# FT232_BreakOutBoard_rev2.net
KiCad netlist of a schematic drawn in EAGLE
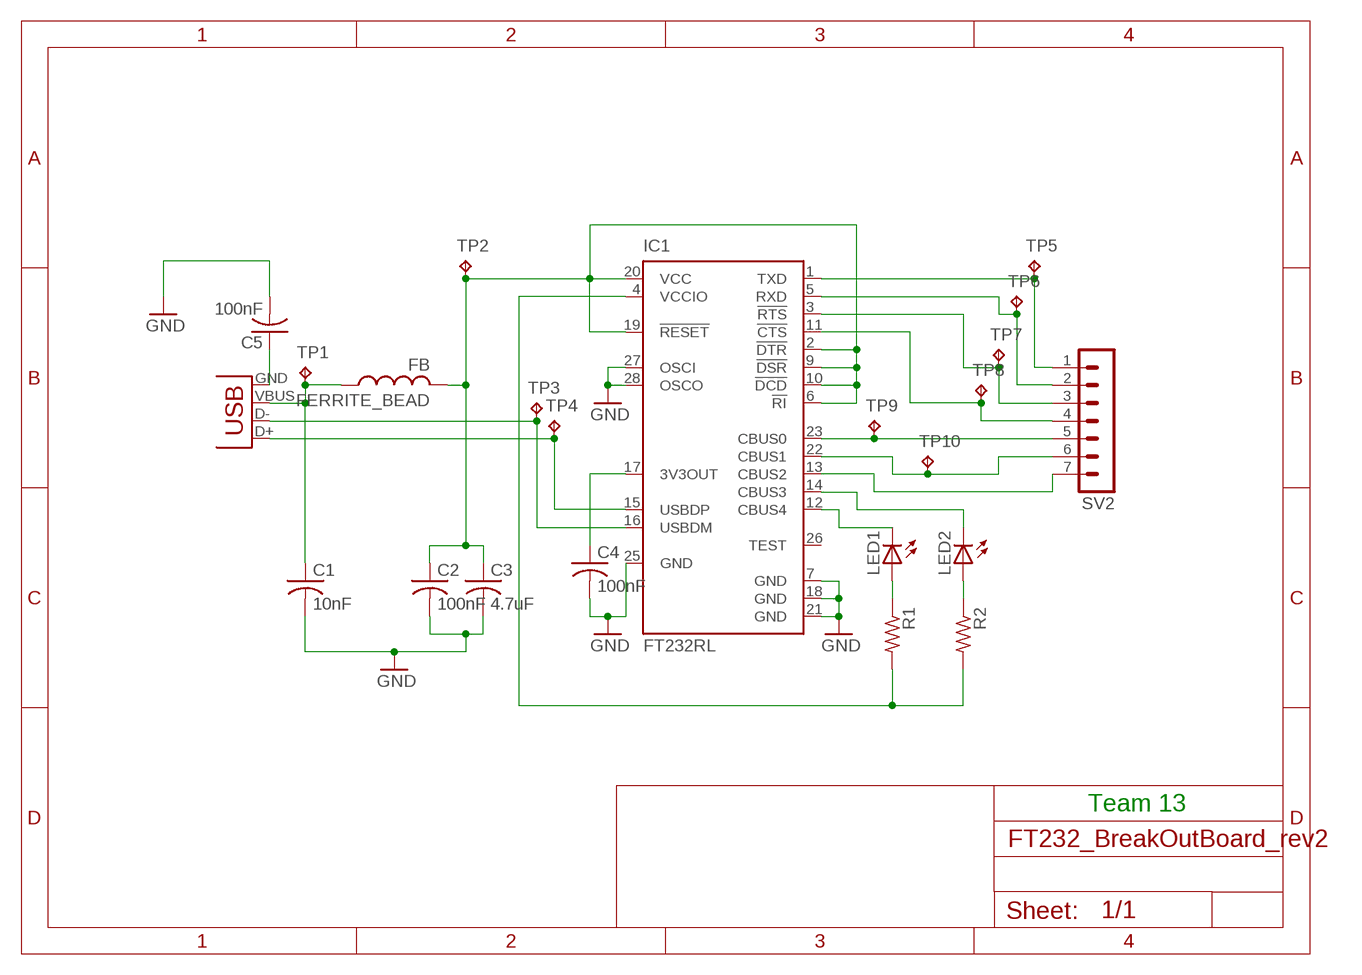
[diagram p0: schematic, sheet 1]

(export (version "E")
  (design (tool "Eeschema 10.0.6"))
  (components
    (comp (ref "C1")
      (value "10nF")
      (footprint "eagle-import:C0805")
      (libsource (lib "eagle-import") (part "C-USC0805"))
    )
    (comp (ref "C2")
      (value "100nF")
      (footprint "eagle-import:C0805")
      (libsource (lib "eagle-import") (part "C-USC0805"))
    )
    (comp (ref "C3")
      (value "4.7uF")
      (footprint "eagle-import:C0805")
      (libsource (lib "eagle-import") (part "C-USC0805"))
    )
    (comp (ref "C4")
      (value "100nF")
      (footprint "eagle-import:C0805")
      (libsource (lib "eagle-import") (part "C-USC0805"))
    )
    (comp (ref "C5")
      (value "100nF")
      (footprint "eagle-import:C0805")
      (libsource (lib "eagle-import") (part "C-USC0805"))
    )
    (comp (ref "FERRITE_BEAD")
      (value "FB")
      (footprint "eagle-import:FB")
      (libsource (lib "eagle-import") (part "FB"))
    )
    (comp (ref "IC1")
      (value "FT232RL")
      (footprint "eagle-import:SSOP28")
      (libsource (lib "eagle-import") (part "FT232RL"))
    )
    (comp (ref "LED1")
      (value "LEDCHIPLED_0805")
      (footprint "eagle-import:CHIPLED_0805")
      (libsource (lib "eagle-import") (part "LEDCHIPLED_0805"))
    )
    (comp (ref "LED2")
      (value "LEDCHIPLED_0805")
      (footprint "eagle-import:CHIPLED_0805")
      (libsource (lib "eagle-import") (part "LEDCHIPLED_0805"))
    )
    (comp (ref "R1")
      (value "R-US_R0805")
      (footprint "eagle-import:R0805")
      (libsource (lib "eagle-import") (part "R-US_R0805"))
    )
    (comp (ref "R2")
      (value "R-US_R0805")
      (footprint "eagle-import:R0805")
      (libsource (lib "eagle-import") (part "R-US_R0805"))
    )
    (comp (ref "SV2")
      (value "MA07-1")
      (footprint "eagle-import:MA07-1")
      (libsource (lib "eagle-import") (part "MA07-1"))
    )
    (comp (ref "TP1")
      (value "TPB1,27")
      (footprint "eagle-import:B1,27")
      (libsource (lib "eagle-import") (part "TPB1,27"))
    )
    (comp (ref "TP2")
      (value "TPB1,27")
      (footprint "eagle-import:B1,27")
      (libsource (lib "eagle-import") (part "TPB1,27"))
    )
    (comp (ref "TP3")
      (value "TPB1,27")
      (footprint "eagle-import:B1,27")
      (libsource (lib "eagle-import") (part "TPB1,27"))
    )
    (comp (ref "TP4")
      (value "TPB1,27")
      (footprint "eagle-import:B1,27")
      (libsource (lib "eagle-import") (part "TPB1,27"))
    )
    (comp (ref "TP5")
      (value "TPB1,27")
      (footprint "eagle-import:B1,27")
      (libsource (lib "eagle-import") (part "TPB1,27"))
    )
    (comp (ref "TP6")
      (value "TPB1,27")
      (footprint "eagle-import:B1,27")
      (libsource (lib "eagle-import") (part "TPB1,27"))
    )
    (comp (ref "TP7")
      (value "TPB1,27")
      (footprint "eagle-import:B1,27")
      (libsource (lib "eagle-import") (part "TPB1,27"))
    )
    (comp (ref "TP8")
      (value "TPB1,27")
      (footprint "eagle-import:B1,27")
      (libsource (lib "eagle-import") (part "TPB1,27"))
    )
    (comp (ref "TP9")
      (value "TPB1,27")
      (footprint "eagle-import:B1,27")
      (libsource (lib "eagle-import") (part "TPB1,27"))
    )
    (comp (ref "TP10")
      (value "TPB1,27")
      (footprint "eagle-import:B1,27")
      (libsource (lib "eagle-import") (part "TPB1,27"))
    )
    (comp (ref "X1")
      (value "USB-B-H")
      (footprint "eagle-import:USB-B-H")
      (libsource (lib "eagle-import") (part "USB-B-H"))
    )
  )
  (nets
    (net (code "1") (name "GND") (class "Default")
      (node (ref "C1") (pin "2") (pinfunction "2_2") (pintype "passive"))
      (node (ref "C2") (pin "2") (pinfunction "2_2") (pintype "passive"))
      (node (ref "C3") (pin "2") (pinfunction "2_2") (pintype "passive"))
      (node (ref "C4") (pin "2") (pinfunction "2_2") (pintype "passive"))
      (node (ref "C5") (pin "2") (pinfunction "2_2") (pintype "passive"))
      (node (ref "IC1") (pin "18") (pinfunction "GND_18") (pintype "power_in"))
      (node (ref "IC1") (pin "21") (pinfunction "GND_21") (pintype "power_in"))
      (node (ref "IC1") (pin "25") (pinfunction "GND_25") (pintype "power_in"))
      (node (ref "IC1") (pin "27") (pinfunction "OSCI_27") (pintype "input"))
      (node (ref "IC1") (pin "28") (pinfunction "OSCO_28") (pintype "output"))
      (node (ref "IC1") (pin "7") (pinfunction "GND_7") (pintype "power_in"))
    )
    (net (code "2") (name "Net-(C5-Pad1)") (class "Default")
      (node (ref "C5") (pin "1") (pinfunction "1_1") (pintype "passive"))
      (node (ref "X1") (pin "GND") (pinfunction "GND_GND") (pintype "bidirectional"))
    )
    (net (code "3") (name "Net-(FERRITE_BEAD-1)") (class "Default")
      (node (ref "C1") (pin "1") (pinfunction "1_1") (pintype "passive"))
      (node (ref "FERRITE_BEAD") (pin "P$1") (pinfunction "1_P$1") (pintype "passive"))
      (node (ref "TP1") (pin "TP") (pinfunction "TP_TP") (pintype "input"))
      (node (ref "X1") (pin "VBUS") (pinfunction "VBUS_VBUS") (pintype "bidirectional"))
    )
    (net (code "4") (name "Net-(FERRITE_BEAD-2)") (class "Default")
      (node (ref "C2") (pin "1") (pinfunction "1_1") (pintype "passive"))
      (node (ref "C3") (pin "1") (pinfunction "1_1") (pintype "passive"))
      (node (ref "FERRITE_BEAD") (pin "P$2") (pinfunction "2_P$2") (pintype "passive"))
      (node (ref "IC1") (pin "10") (pinfunction "~{DCD}_10") (pintype "input"))
      (node (ref "IC1") (pin "19") (pinfunction "~{RESET}_19") (pintype "input"))
      (node (ref "IC1") (pin "2") (pinfunction "~{DTR}_2") (pintype "output"))
      (node (ref "IC1") (pin "20") (pinfunction "VCC_20") (pintype "power_in"))
      (node (ref "IC1") (pin "6") (pinfunction "~{RI}_6") (pintype "input"))
      (node (ref "IC1") (pin "9") (pinfunction "~{DSR}_9") (pintype "input"))
      (node (ref "TP2") (pin "TP") (pinfunction "TP_TP") (pintype "input"))
    )
    (net (code "5") (name "Net-(IC1-3V3OUT)") (class "Default")
      (node (ref "C4") (pin "1") (pinfunction "1_1") (pintype "passive"))
      (node (ref "IC1") (pin "17") (pinfunction "3V3OUT_17") (pintype "output"))
    )
    (net (code "6") (name "Net-(IC1-CBUS0)") (class "Default")
      (node (ref "IC1") (pin "23") (pinfunction "CBUS0_23") (pintype "bidirectional"))
      (node (ref "SV2") (pin "5") (pinfunction "5_5") (pintype "passive"))
      (node (ref "TP9") (pin "TP") (pinfunction "TP_TP") (pintype "input"))
    )
    (net (code "7") (name "Net-(IC1-CBUS1)") (class "Default")
      (node (ref "IC1") (pin "22") (pinfunction "CBUS1_22") (pintype "bidirectional"))
      (node (ref "SV2") (pin "6") (pinfunction "6_6") (pintype "passive"))
      (node (ref "TP10") (pin "TP") (pinfunction "TP_TP") (pintype "input"))
    )
    (net (code "8") (name "Net-(IC1-CBUS2)") (class "Default")
      (node (ref "IC1") (pin "13") (pinfunction "CBUS2_13") (pintype "bidirectional"))
      (node (ref "SV2") (pin "7") (pinfunction "7_7") (pintype "passive"))
    )
    (net (code "9") (name "Net-(IC1-CBUS3)") (class "Default")
      (node (ref "IC1") (pin "14") (pinfunction "CBUS3_14") (pintype "bidirectional"))
      (node (ref "LED2") (pin "C") (pinfunction "C_C") (pintype "passive"))
    )
    (net (code "10") (name "Net-(IC1-CBUS4)") (class "Default")
      (node (ref "IC1") (pin "12") (pinfunction "CBUS4_12") (pintype "bidirectional"))
      (node (ref "LED1") (pin "C") (pinfunction "C_C") (pintype "passive"))
    )
    (net (code "11") (name "Net-(IC1-RXD)") (class "Default")
      (node (ref "IC1") (pin "5") (pinfunction "RXD_5") (pintype "input"))
      (node (ref "SV2") (pin "2") (pinfunction "2_2") (pintype "passive"))
      (node (ref "TP6") (pin "TP") (pinfunction "TP_TP") (pintype "input"))
    )
    (net (code "12") (name "Net-(IC1-TXD)") (class "Default")
      (node (ref "IC1") (pin "1") (pinfunction "TXD_1") (pintype "output"))
      (node (ref "SV2") (pin "1") (pinfunction "1_1") (pintype "passive"))
      (node (ref "TP5") (pin "TP") (pinfunction "TP_TP") (pintype "input"))
    )
    (net (code "13") (name "Net-(IC1-USBDM)") (class "Default")
      (node (ref "IC1") (pin "16") (pinfunction "USBDM_16") (pintype "bidirectional"))
      (node (ref "TP3") (pin "TP") (pinfunction "TP_TP") (pintype "input"))
      (node (ref "X1") (pin "D-") (pinfunction "D-_D-") (pintype "bidirectional"))
    )
    (net (code "14") (name "Net-(IC1-USBDP)") (class "Default")
      (node (ref "IC1") (pin "15") (pinfunction "USBDP_15") (pintype "bidirectional"))
      (node (ref "TP4") (pin "TP") (pinfunction "TP_TP") (pintype "input"))
      (node (ref "X1") (pin "D+") (pinfunction "D+_D+") (pintype "bidirectional"))
    )
    (net (code "15") (name "Net-(IC1-VCCIO)") (class "Default")
      (node (ref "IC1") (pin "4") (pinfunction "VCCIO_4") (pintype "power_in"))
      (node (ref "R1") (pin "2") (pinfunction "2_2") (pintype "passive"))
      (node (ref "R2") (pin "2") (pinfunction "2_2") (pintype "passive"))
    )
    (net (code "16") (name "Net-(IC1-~{CTS})") (class "Default")
      (node (ref "IC1") (pin "11") (pinfunction "~{CTS}_11") (pintype "input"))
      (node (ref "SV2") (pin "4") (pinfunction "4_4") (pintype "passive"))
      (node (ref "TP8") (pin "TP") (pinfunction "TP_TP") (pintype "input"))
    )
    (net (code "17") (name "Net-(IC1-~{RTS})") (class "Default")
      (node (ref "IC1") (pin "3") (pinfunction "~{RTS}_3") (pintype "output"))
      (node (ref "SV2") (pin "3") (pinfunction "3_3") (pintype "passive"))
      (node (ref "TP7") (pin "TP") (pinfunction "TP_TP") (pintype "input"))
    )
    (net (code "18") (name "Net-(LED1-PadA)") (class "Default")
      (node (ref "LED1") (pin "A") (pinfunction "A_A") (pintype "passive"))
      (node (ref "R1") (pin "1") (pinfunction "1_1") (pintype "passive"))
    )
    (net (code "19") (name "Net-(LED2-PadA)") (class "Default")
      (node (ref "LED2") (pin "A") (pinfunction "A_A") (pintype "passive"))
      (node (ref "R2") (pin "1") (pinfunction "1_1") (pintype "passive"))
    )
    (net (code "20") (name "unconnected-(IC1-TEST-Pad26)") (class "Default")
      (node (ref "IC1") (pin "26") (pinfunction "TEST_26") (pintype "input"))
    )
  )
)
